# Bussiness_Card_Easyeda.net
KiCad netlist of a schematic drawn in EasyEDA Pro
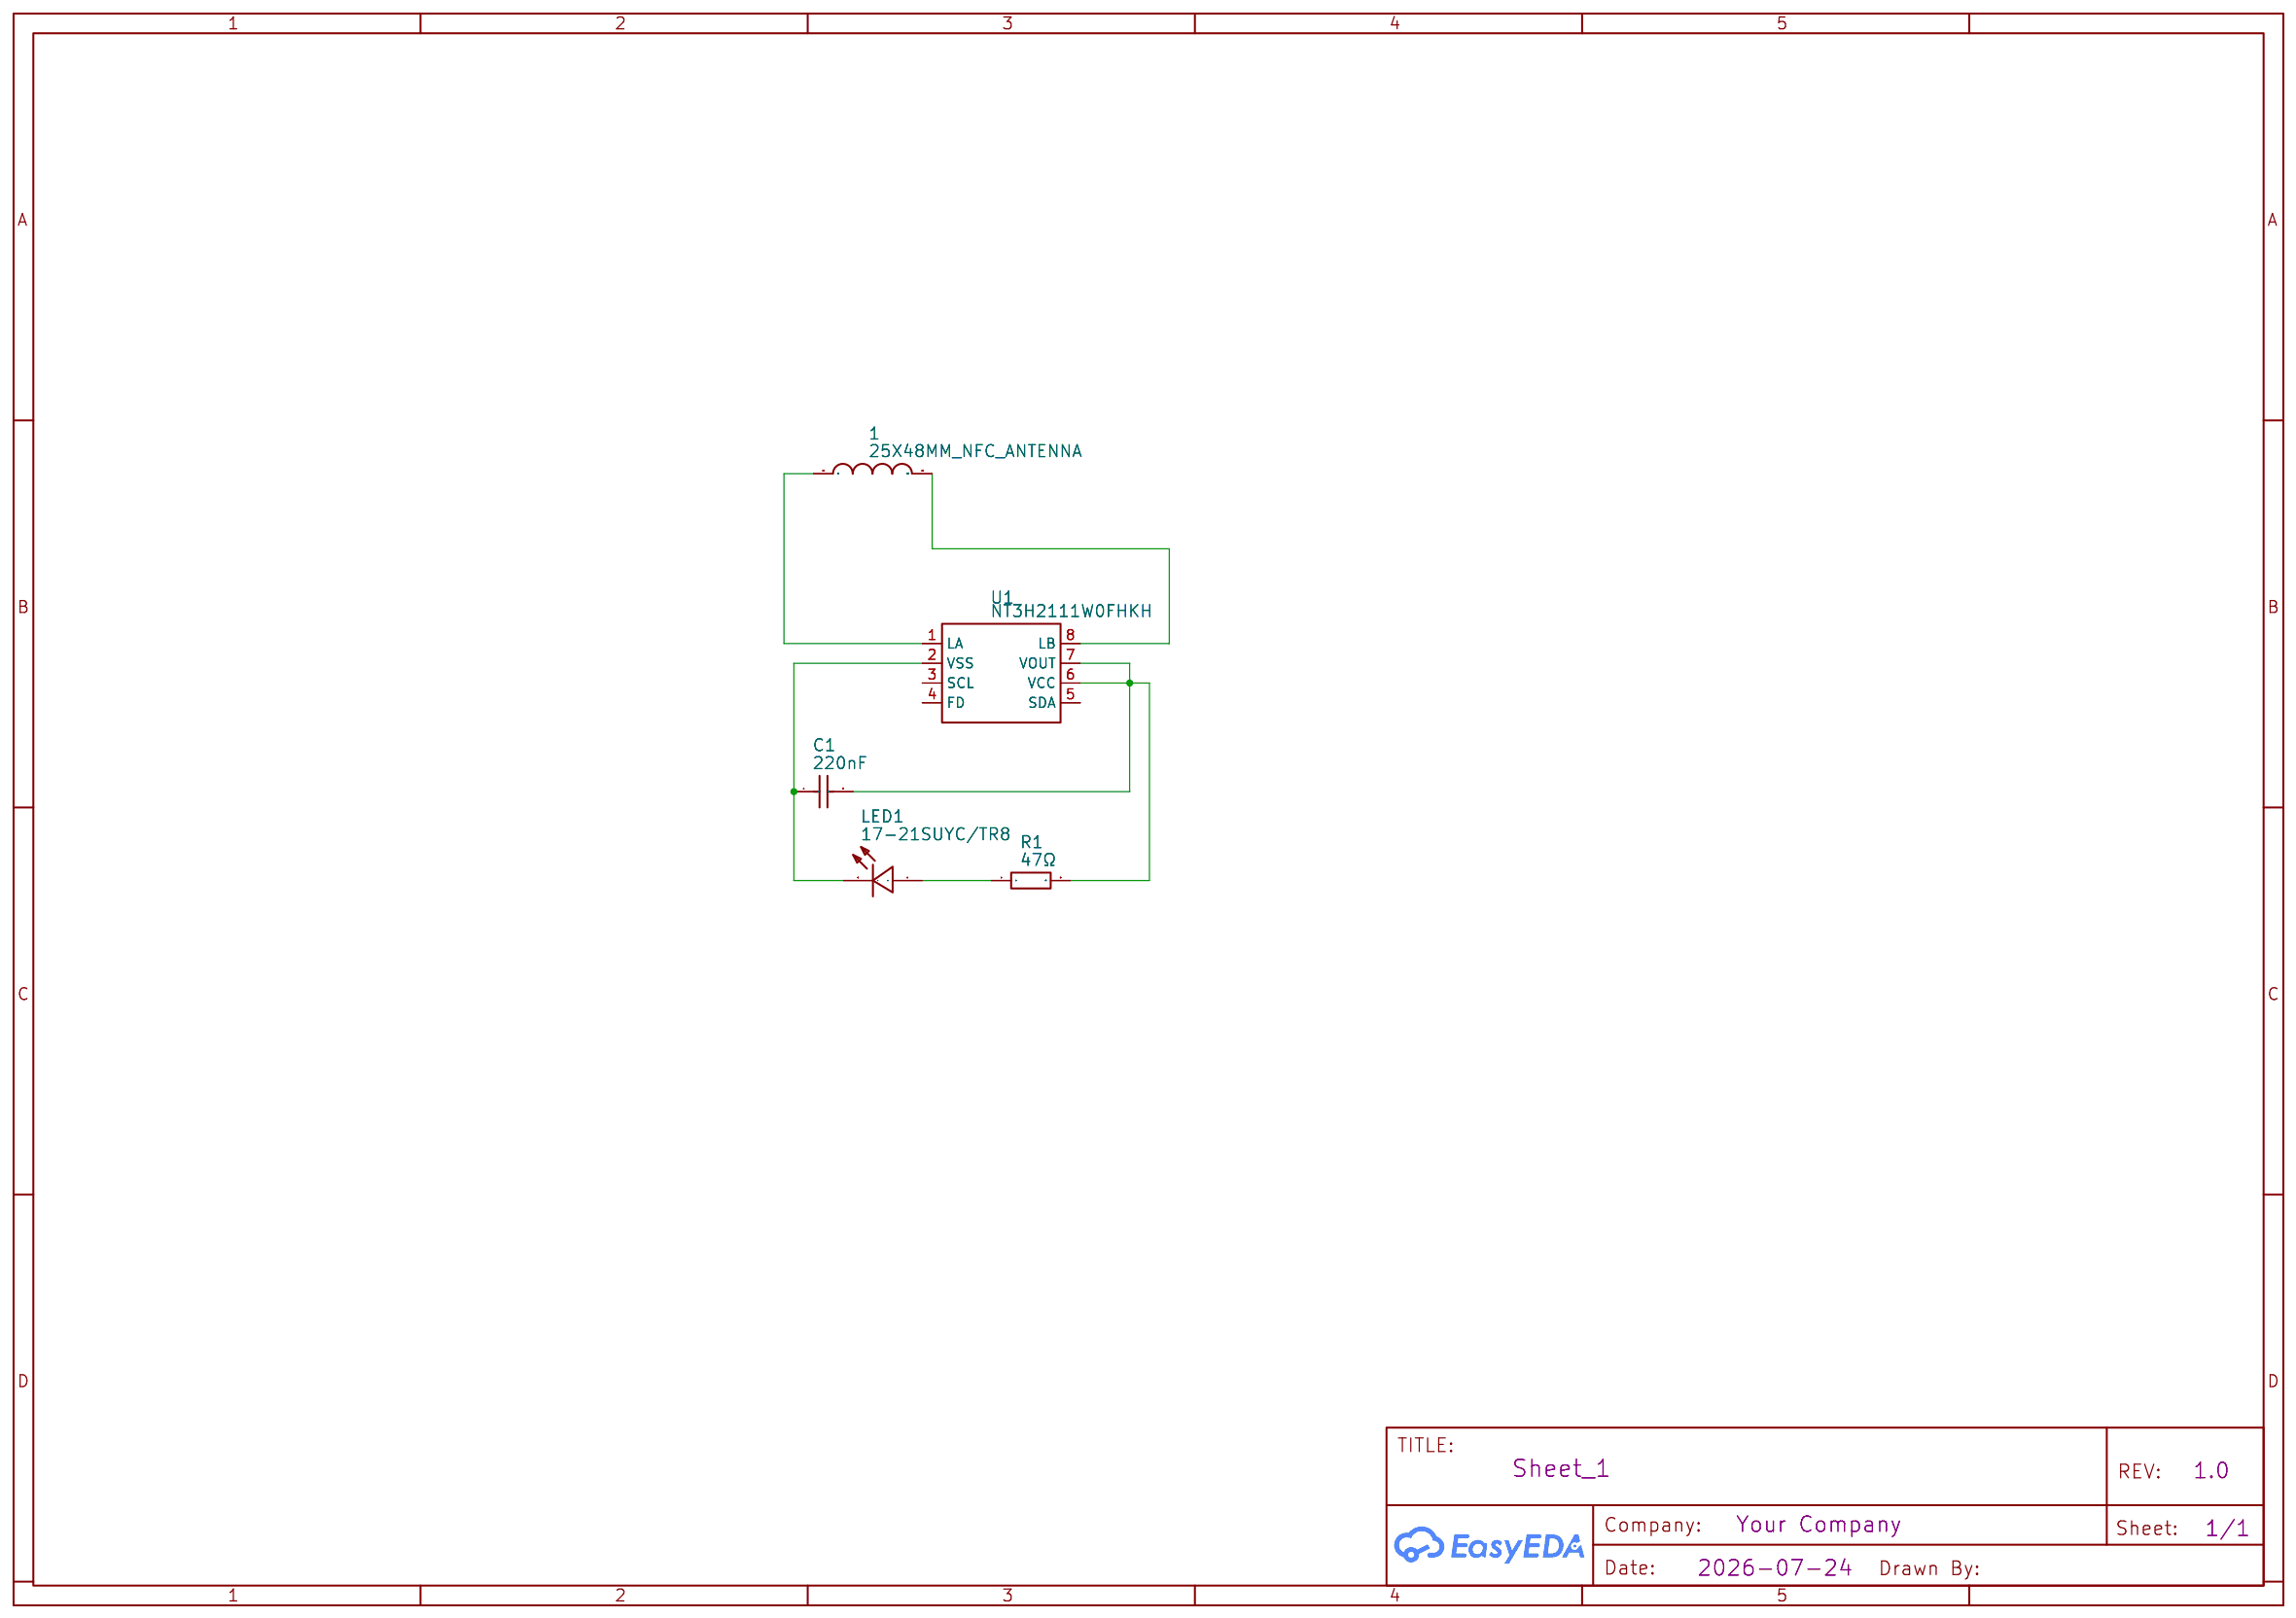
[diagram p0: schematic sheet]

(export (version "E")
  (design (tool "Eeschema 10.0.6"))
  (components
    (comp (ref "1")
      (value "25X48MM_NFC_ANTENNA")
      (footprint "easyedapro:25X48MM_NFC_ANTENNA")
      (libsource (lib "easyedapro") (part "25X48MM_NFC_ANTENNA"))
    )
    (comp (ref "C1")
      (value "220nF")
      (footprint "easyedapro:C0603")
      (fields
        (field (name "Manufacturer Part") "CL10B224KA8NNNC")
        (field (name "Manufacturer") "SAMSUNG(三星)")
      )
      (libsource (lib "easyedapro") (part "220nF"))
    )
    (comp (ref "LED1")
      (value "17-21SUYC/TR8")
      (footprint "easyedapro:LED0805-R-RD")
      (fields (field (name "Manufacturer Part") "KT-0805黄灯") (field (name "Manufacturer") "KENTO"))
      (libsource (lib "easyedapro") (part "17-21SUYC/TR8"))
    )
    (comp (ref "R1")
      (value "47Ω")
      (footprint "easyedapro:R0603")
      (fields
        (field (name "Manufacturer Part") "0603WAF470JT5E")
        (field (name "Manufacturer") "UNI-ROYAL(厚声)")
      )
      (libsource (lib "easyedapro") (part "47Ω"))
    )
    (comp (ref "U1")
      (value "NT3H2111W0FHKH")
      (footprint "easyedapro:XQFN-8_L1.6-W1.6-P0.50-BL_NT3H2111W0FHKH")
      (fields (field (name "Manufacturer") "NXP(恩智浦)"))
      (libsource (lib "easyedapro") (part "NT3H2111W0FHKH"))
    )
  )
  (nets
    (net (code "1") (name "Net-(LED1-+)") (class "Default")
      (node (ref "LED1") (pin "1") (pinfunction "+_1") (pintype "unspecified"))
      (node (ref "R1") (pin "1") (pinfunction "1_1") (pintype "input"))
    )
    (net (code "2") (name "Net-(LED1--)") (class "Default")
      (node (ref "C1") (pin "1") (pinfunction "1_1") (pintype "input"))
      (node (ref "LED1") (pin "2") (pinfunction "-_2") (pintype "unspecified"))
      (node (ref "U1") (pin "2") (pinfunction "VSS_2") (pintype "unspecified"))
    )
    (net (code "3") (name "Net-(U1-LA)") (class "Default")
      (node (ref "1") (pin "P$1") (pinfunction "P$1_P$1") (pintype "bidirectional"))
      (node (ref "U1") (pin "1") (pinfunction "LA_1") (pintype "unspecified"))
    )
    (net (code "4") (name "Net-(U1-LB)") (class "Default")
      (node (ref "1") (pin "P$2") (pinfunction "P$2_P$2") (pintype "bidirectional"))
      (node (ref "U1") (pin "8") (pinfunction "LB_8") (pintype "unspecified"))
    )
    (net (code "5") (name "Net-(U1-VCC)") (class "Default")
      (node (ref "C1") (pin "2") (pinfunction "2_2") (pintype "input"))
      (node (ref "R1") (pin "2") (pinfunction "2_2") (pintype "input"))
      (node (ref "U1") (pin "6") (pinfunction "VCC_6") (pintype "unspecified"))
      (node (ref "U1") (pin "7") (pinfunction "VOUT_7") (pintype "unspecified"))
    )
    (net (code "6") (name "unconnected-(U1-FD-Pad4)") (class "Default")
      (node (ref "U1") (pin "4") (pinfunction "FD_4") (pintype "unspecified"))
    )
    (net (code "7") (name "unconnected-(U1-SCL-Pad3)") (class "Default")
      (node (ref "U1") (pin "3") (pinfunction "SCL_3") (pintype "unspecified"))
    )
    (net (code "8") (name "unconnected-(U1-SDA-Pad5)") (class "Default")
      (node (ref "U1") (pin "5") (pinfunction "SDA_5") (pintype "unspecified"))
    )
  )
)
